# 12V_to_5V_LDO_1A.net
KiCad netlist of a schematic drawn in Altium Designer
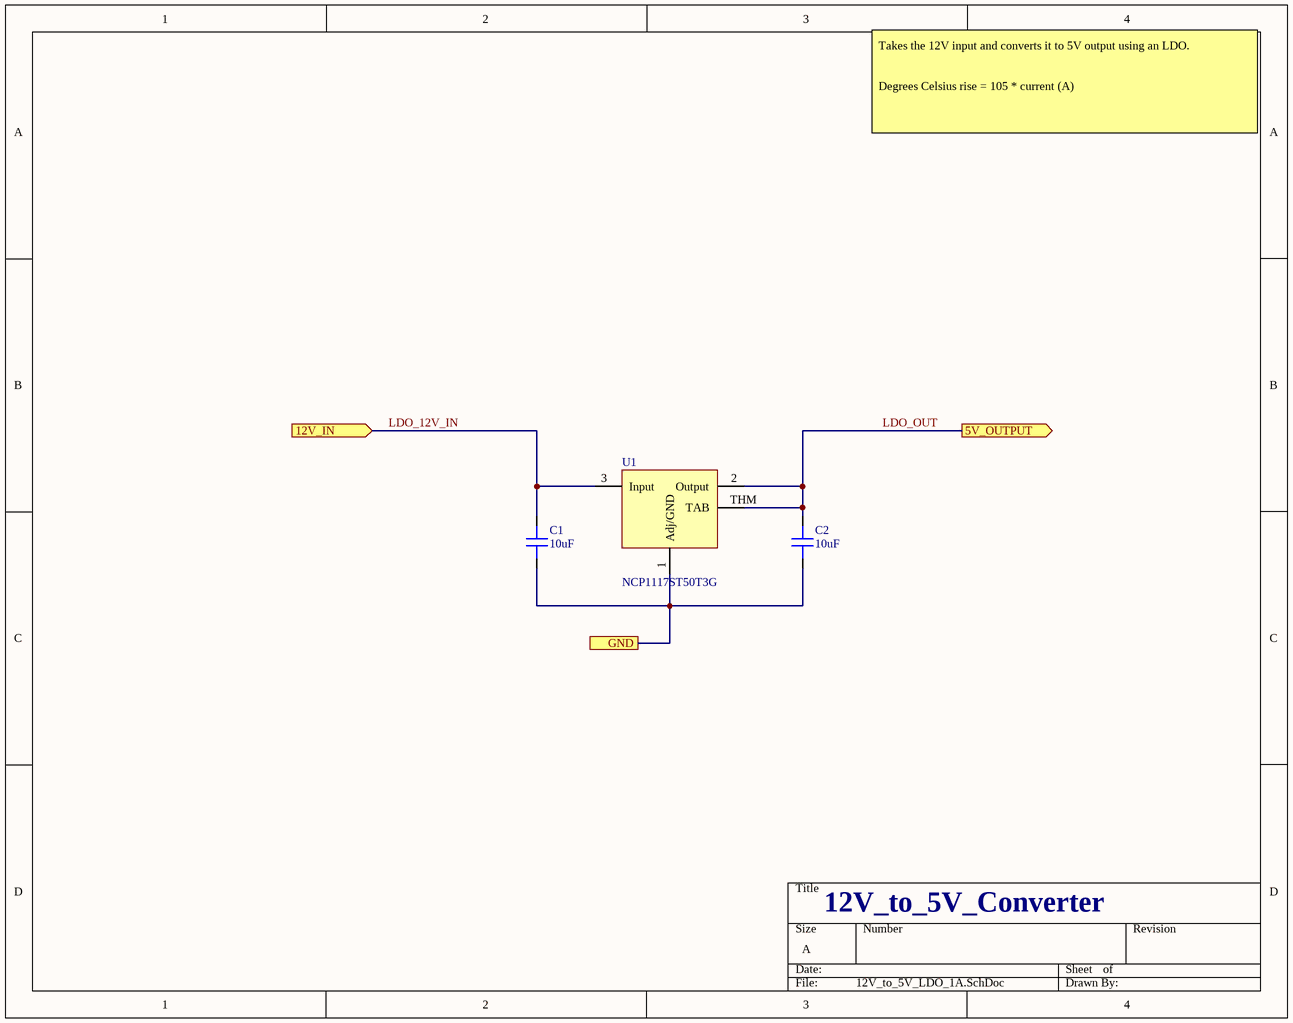
[diagram p0: 12V_to_5V_LDO_1A.SchDoc]

(export (version "E")
  (design (tool "Eeschema 10.0.6"))
  (components
    (comp (ref "C1")
      (value "capacitor")
      (footprint "0603")
      (description "Generic 0603 capacitor")
      (fields (field (name "CAPACITANCE") "10uF") (field (name "VOLTAGE") "50"))
      (libsource (lib "altlib") (part "capacitor"))
    )
    (comp (ref "C2")
      (value "capacitor")
      (footprint "0603")
      (description "Generic 0603 capacitor")
      (fields (field (name "CAPACITANCE") "10uF") (field (name "VOLTAGE") "50"))
      (libsource (lib "altlib") (part "capacitor"))
    )
    (comp (ref "U1")
      (value "NCP1117ST50T3G")
      (footprint "SOT-223-3")
      (description "5V linear regulator")
      (libsource (lib "altlib") (part "NCP1117ST50T3G"))
    )
  )
  (nets
    (net (code "1") (name "/GND") (class "Default")
      (node (ref "C1") (pin "1") (pinfunction "1_1") (pintype "passive"))
      (node (ref "C2") (pin "1") (pinfunction "1_1") (pintype "passive"))
      (node (ref "U1") (pin "1") (pinfunction "Adj/GND_1") (pintype "passive"))
    )
    (net (code "2") (name "/LDO_12V_IN") (class "Default")
      (node (ref "C1") (pin "2") (pinfunction "2_2") (pintype "passive"))
      (node (ref "U1") (pin "3") (pinfunction "Input_3") (pintype "passive"))
    )
    (net (code "3") (name "/LDO_OUT") (class "Default")
      (node (ref "C2") (pin "2") (pinfunction "2_2") (pintype "passive"))
      (node (ref "U1") (pin "2") (pinfunction "Output_2") (pintype "passive"))
      (node (ref "U1") (pin "THM") (pinfunction "TAB_THM") (pintype "passive"))
    )
  )
)
